# BusRCServo.net
KiCad netlist of a schematic drawn in Altium Designer
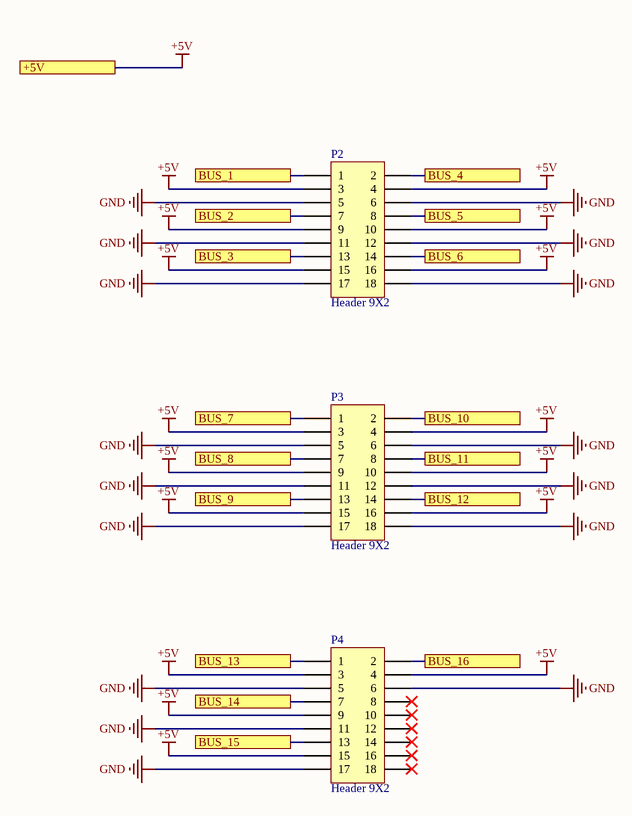
[diagram p0: BusRCServo.SchDoc]

(export (version "E")
  (design (tool "Eeschema 10.0.6"))
  (components
    (comp (ref "P2")
      (value "Header 9X2")
      (footprint "HDR2X9")
      (description "Header, 9-Pin, Dual row")
      (fields (field (name "PUBLISHER") "Altium Limited"))
      (libsource (lib "BKIT4U_LIB") (part "Header 9X2"))
    )
    (comp (ref "P3")
      (value "Header 9X2")
      (footprint "HDR2X9")
      (description "Header, 9-Pin, Dual row")
      (fields (field (name "PUBLISHER") "Altium Limited"))
      (libsource (lib "BKIT4U_LIB") (part "Header 9X2"))
    )
    (comp (ref "P4")
      (value "Header 9X2")
      (footprint "HDR2X9")
      (description "Header, 9-Pin, Dual row")
      (fields (field (name "PUBLISHER") "Altium Limited"))
      (libsource (lib "BKIT4U_LIB") (part "Header 9X2"))
    )
  )
  (nets
    (net (code "1") (name "+5V") (class "Default")
      (node (ref "P2") (pin "10") (pinfunction "10_10") (pintype "passive"))
      (node (ref "P2") (pin "15") (pinfunction "15_15") (pintype "passive"))
      (node (ref "P2") (pin "16") (pinfunction "16_16") (pintype "passive"))
      (node (ref "P2") (pin "3") (pinfunction "3_3") (pintype "passive"))
      (node (ref "P2") (pin "4") (pinfunction "4_4") (pintype "passive"))
      (node (ref "P2") (pin "9") (pinfunction "9_9") (pintype "passive"))
      (node (ref "P3") (pin "10") (pinfunction "10_10") (pintype "passive"))
      (node (ref "P3") (pin "15") (pinfunction "15_15") (pintype "passive"))
      (node (ref "P3") (pin "16") (pinfunction "16_16") (pintype "passive"))
      (node (ref "P3") (pin "3") (pinfunction "3_3") (pintype "passive"))
      (node (ref "P3") (pin "4") (pinfunction "4_4") (pintype "passive"))
      (node (ref "P3") (pin "9") (pinfunction "9_9") (pintype "passive"))
      (node (ref "P4") (pin "15") (pinfunction "15_15") (pintype "passive"))
      (node (ref "P4") (pin "3") (pinfunction "3_3") (pintype "passive"))
      (node (ref "P4") (pin "4") (pinfunction "4_4") (pintype "passive"))
      (node (ref "P4") (pin "9") (pinfunction "9_9") (pintype "passive"))
    )
    (net (code "2") (name "/BUS_1") (class "Default")
      (node (ref "P2") (pin "1") (pinfunction "1_1") (pintype "passive"))
    )
    (net (code "3") (name "/BUS_2") (class "Default")
      (node (ref "P2") (pin "7") (pinfunction "7_7") (pintype "passive"))
    )
    (net (code "4") (name "/BUS_3") (class "Default")
      (node (ref "P2") (pin "13") (pinfunction "13_13") (pintype "passive"))
    )
    (net (code "5") (name "/BUS_4") (class "Default")
      (node (ref "P2") (pin "2") (pinfunction "2_2") (pintype "passive"))
    )
    (net (code "6") (name "/BUS_5") (class "Default")
      (node (ref "P2") (pin "8") (pinfunction "8_8") (pintype "passive"))
    )
    (net (code "7") (name "/BUS_6") (class "Default")
      (node (ref "P2") (pin "14") (pinfunction "14_14") (pintype "passive"))
    )
    (net (code "8") (name "/BUS_7") (class "Default")
      (node (ref "P3") (pin "1") (pinfunction "1_1") (pintype "passive"))
    )
    (net (code "9") (name "/BUS_8") (class "Default")
      (node (ref "P3") (pin "7") (pinfunction "7_7") (pintype "passive"))
    )
    (net (code "10") (name "/BUS_9") (class "Default")
      (node (ref "P3") (pin "13") (pinfunction "13_13") (pintype "passive"))
    )
    (net (code "11") (name "/BUS_10") (class "Default")
      (node (ref "P3") (pin "2") (pinfunction "2_2") (pintype "passive"))
    )
    (net (code "12") (name "/BUS_11") (class "Default")
      (node (ref "P3") (pin "8") (pinfunction "8_8") (pintype "passive"))
    )
    (net (code "13") (name "/BUS_12") (class "Default")
      (node (ref "P3") (pin "14") (pinfunction "14_14") (pintype "passive"))
    )
    (net (code "14") (name "/BUS_13") (class "Default")
      (node (ref "P4") (pin "1") (pinfunction "1_1") (pintype "passive"))
    )
    (net (code "15") (name "/BUS_14") (class "Default")
      (node (ref "P4") (pin "7") (pinfunction "7_7") (pintype "passive"))
    )
    (net (code "16") (name "/BUS_15") (class "Default")
      (node (ref "P4") (pin "13") (pinfunction "13_13") (pintype "passive"))
    )
    (net (code "17") (name "/BUS_16") (class "Default")
      (node (ref "P4") (pin "2") (pinfunction "2_2") (pintype "passive"))
    )
    (net (code "18") (name "GND") (class "Default")
      (node (ref "P2") (pin "11") (pinfunction "11_11") (pintype "passive"))
      (node (ref "P2") (pin "12") (pinfunction "12_12") (pintype "passive"))
      (node (ref "P2") (pin "17") (pinfunction "17_17") (pintype "passive"))
      (node (ref "P2") (pin "18") (pinfunction "18_18") (pintype "passive"))
      (node (ref "P2") (pin "5") (pinfunction "5_5") (pintype "passive"))
      (node (ref "P2") (pin "6") (pinfunction "6_6") (pintype "passive"))
      (node (ref "P3") (pin "11") (pinfunction "11_11") (pintype "passive"))
      (node (ref "P3") (pin "12") (pinfunction "12_12") (pintype "passive"))
      (node (ref "P3") (pin "17") (pinfunction "17_17") (pintype "passive"))
      (node (ref "P3") (pin "18") (pinfunction "18_18") (pintype "passive"))
      (node (ref "P3") (pin "5") (pinfunction "5_5") (pintype "passive"))
      (node (ref "P3") (pin "6") (pinfunction "6_6") (pintype "passive"))
      (node (ref "P4") (pin "11") (pinfunction "11_11") (pintype "passive"))
      (node (ref "P4") (pin "17") (pinfunction "17_17") (pintype "passive"))
      (node (ref "P4") (pin "5") (pinfunction "5_5") (pintype "passive"))
      (node (ref "P4") (pin "6") (pinfunction "6_6") (pintype "passive"))
    )
    (net (code "19") (name "unconnected-(P4-Pad8)") (class "Default")
      (node (ref "P4") (pin "8") (pinfunction "8_8") (pintype "passive+no_connect"))
    )
    (net (code "20") (name "unconnected-(P4-Pad10)") (class "Default")
      (node (ref "P4") (pin "10") (pinfunction "10_10") (pintype "passive+no_connect"))
    )
    (net (code "21") (name "unconnected-(P4-Pad12)") (class "Default")
      (node (ref "P4") (pin "12") (pinfunction "12_12") (pintype "passive+no_connect"))
    )
    (net (code "22") (name "unconnected-(P4-Pad14)") (class "Default")
      (node (ref "P4") (pin "14") (pinfunction "14_14") (pintype "passive+no_connect"))
    )
    (net (code "23") (name "unconnected-(P4-Pad16)") (class "Default")
      (node (ref "P4") (pin "16") (pinfunction "16_16") (pintype "passive+no_connect"))
    )
    (net (code "24") (name "unconnected-(P4-Pad18)") (class "Default")
      (node (ref "P4") (pin "18") (pinfunction "18_18") (pintype "passive+no_connect"))
    )
  )
)
